# Power-MCU-Breakout.net
KiCad netlist of a schematic drawn in Altium Designer
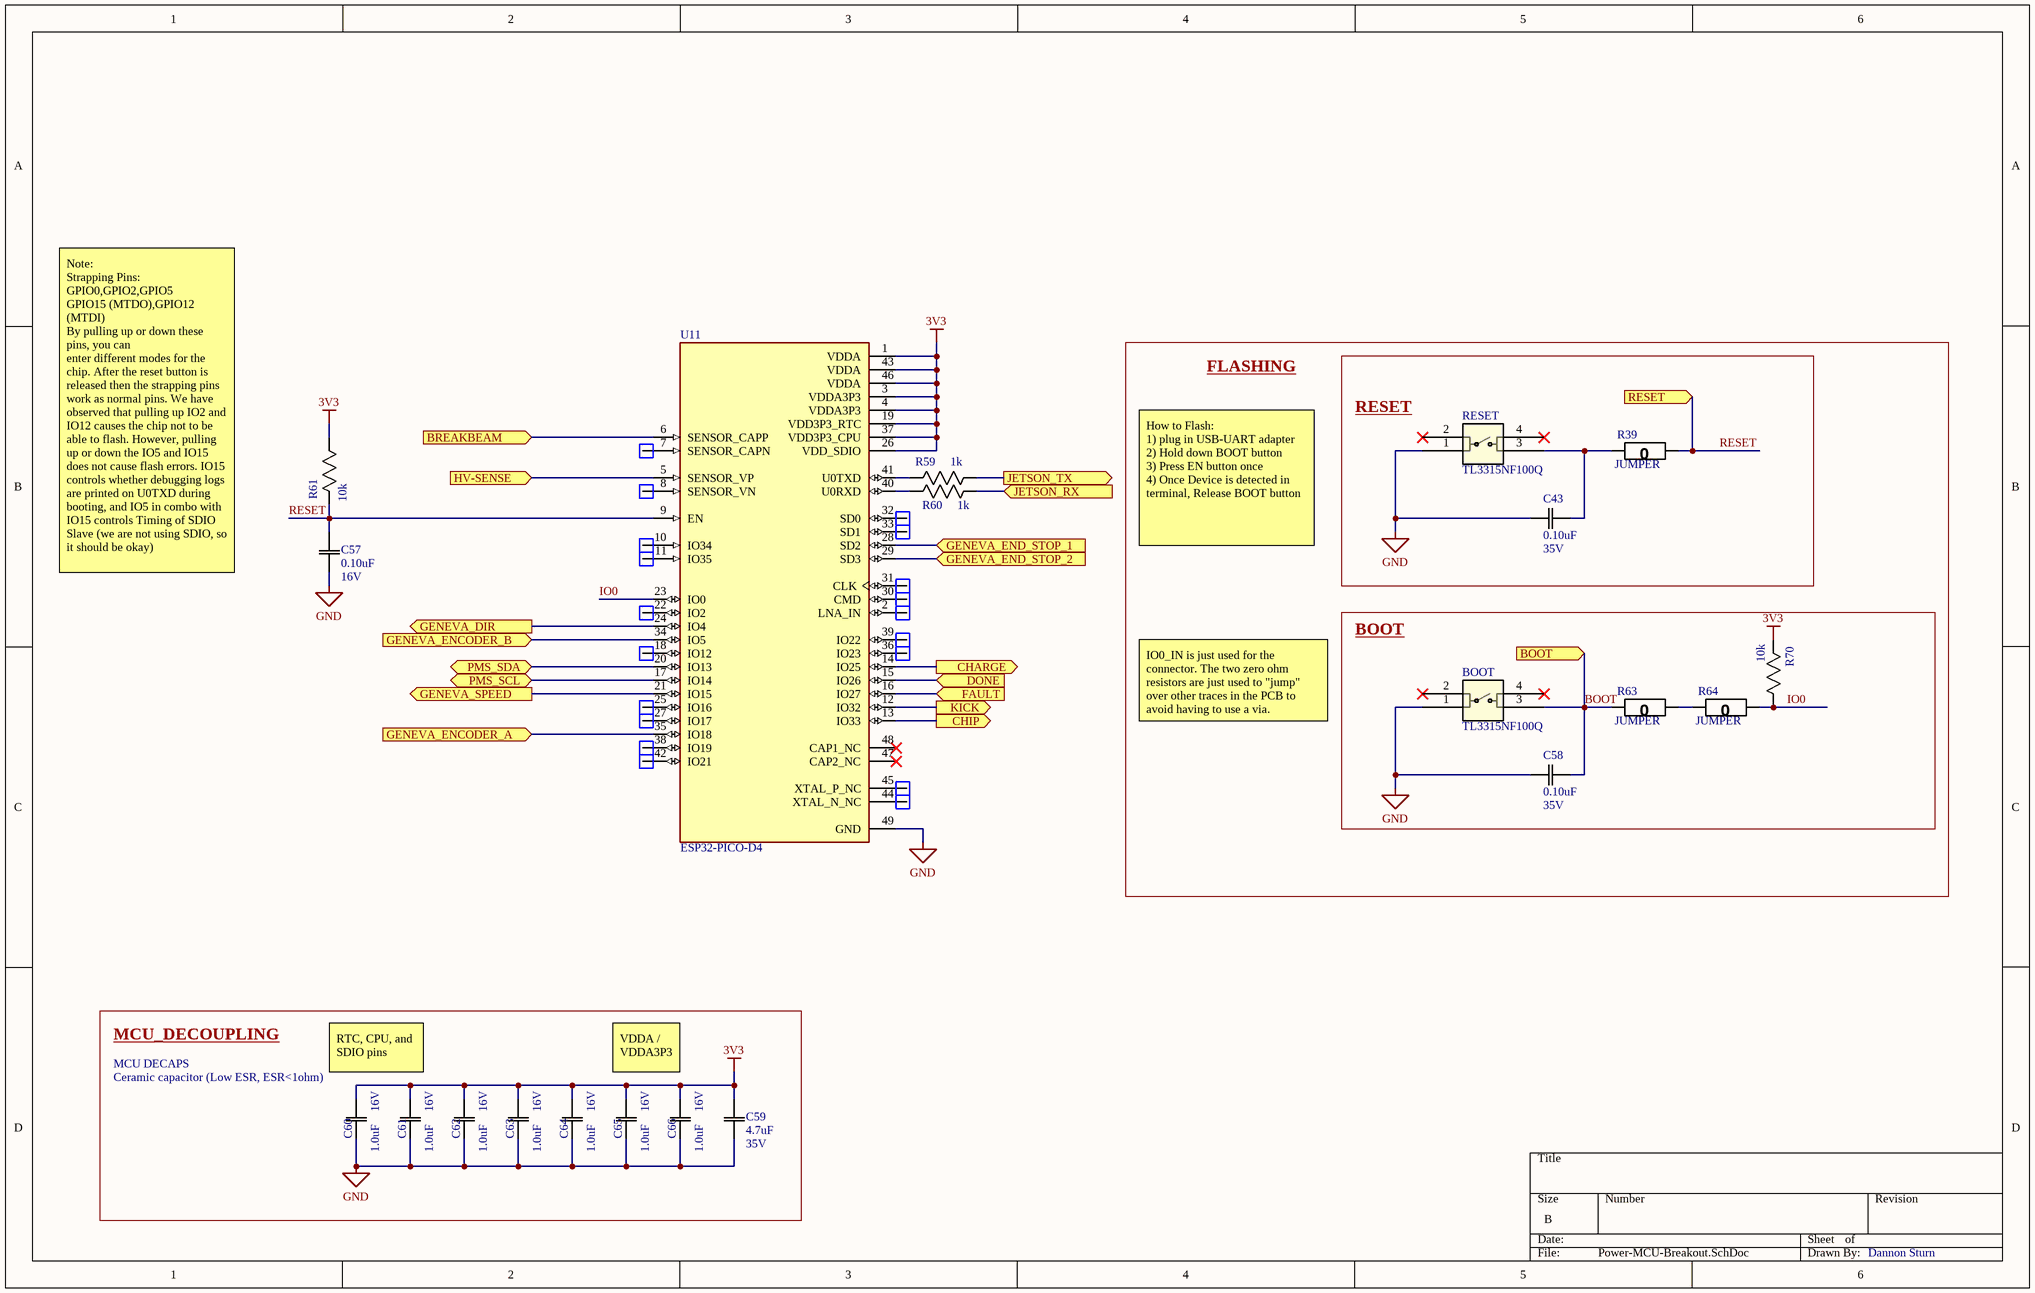
[diagram p0: Power-MCU-Breakout.SchDoc]

(export (version "E")
  (design (tool "Eeschema 10.0.6"))
  (components
    (comp (ref "1")
      (value "Breakout Pin 0603")
      (footprint "BreakoutPin 0603")
      (description "0603 breakout pad")
      (libsource (lib "IC_Library") (part "Breakout Pin 0603"))
    )
    (comp (ref "2")
      (value "Breakout Pin 0603")
      (footprint "BreakoutPin 0603")
      (description "0603 breakout pad")
      (libsource (lib "IC_Library") (part "Breakout Pin 0603"))
    )
    (comp (ref "3")
      (value "Breakout Pin 0603")
      (footprint "BreakoutPin 0603")
      (description "0603 breakout pad")
      (libsource (lib "IC_Library") (part "Breakout Pin 0603"))
    )
    (comp (ref "7")
      (value "Breakout Pin 0603")
      (footprint "BreakoutPin 0603")
      (description "0603 breakout pad")
      (libsource (lib "IC_Library") (part "Breakout Pin 0603"))
    )
    (comp (ref "8")
      (value "Breakout Pin 0603")
      (footprint "BreakoutPin 0603")
      (description "0603 breakout pad")
      (libsource (lib "IC_Library") (part "Breakout Pin 0603"))
    )
    (comp (ref "10")
      (value "Breakout Pin 0603")
      (footprint "BreakoutPin 0603")
      (description "0603 breakout pad")
      (libsource (lib "IC_Library") (part "Breakout Pin 0603"))
    )
    (comp (ref "11")
      (value "Breakout Pin 0603")
      (footprint "BreakoutPin 0603")
      (description "0603 breakout pad")
      (libsource (lib "IC_Library") (part "Breakout Pin 0603"))
    )
    (comp (ref "18")
      (value "Breakout Pin 0603")
      (footprint "BreakoutPin 0603")
      (description "0603 breakout pad")
      (libsource (lib "IC_Library") (part "Breakout Pin 0603"))
    )
    (comp (ref "22")
      (value "Breakout Pin 0603")
      (footprint "BreakoutPin 0603")
      (description "0603 breakout pad")
      (libsource (lib "IC_Library") (part "Breakout Pin 0603"))
    )
    (comp (ref "25")
      (value "Breakout Pin 0603")
      (footprint "BreakoutPin 0603")
      (description "0603 breakout pad")
      (libsource (lib "IC_Library") (part "Breakout Pin 0603"))
    )
    (comp (ref "27")
      (value "Breakout Pin 0603")
      (footprint "BreakoutPin 0603")
      (description "0603 breakout pad")
      (libsource (lib "IC_Library") (part "Breakout Pin 0603"))
    )
    (comp (ref "30")
      (value "Breakout Pin 0603")
      (footprint "BreakoutPin 0603")
      (description "0603 breakout pad")
      (libsource (lib "IC_Library") (part "Breakout Pin 0603"))
    )
    (comp (ref "31")
      (value "Breakout Pin 0603")
      (footprint "BreakoutPin 0603")
      (description "0603 breakout pad")
      (libsource (lib "IC_Library") (part "Breakout Pin 0603"))
    )
    (comp (ref "32")
      (value "Breakout Pin 0603")
      (footprint "BreakoutPin 0603")
      (description "0603 breakout pad")
      (libsource (lib "IC_Library") (part "Breakout Pin 0603"))
    )
    (comp (ref "33")
      (value "Breakout Pin 0603")
      (footprint "BreakoutPin 0603")
      (description "0603 breakout pad")
      (libsource (lib "IC_Library") (part "Breakout Pin 0603"))
    )
    (comp (ref "36")
      (value "Breakout Pin 0603")
      (footprint "BreakoutPin 0603")
      (description "0603 breakout pad")
      (libsource (lib "IC_Library") (part "Breakout Pin 0603"))
    )
    (comp (ref "42")
      (value "Breakout Pin 0603")
      (footprint "BreakoutPin 0603")
      (description "0603 breakout pad")
      (libsource (lib "IC_Library") (part "Breakout Pin 0603"))
    )
    (comp (ref "44")
      (value "Breakout Pin 0603")
      (footprint "BreakoutPin 0603")
      (description "0603 breakout pad")
      (libsource (lib "IC_Library") (part "Breakout Pin 0603"))
    )
    (comp (ref "45")
      (value "Breakout Pin 0603")
      (footprint "BreakoutPin 0603")
      (description "0603 breakout pad")
      (libsource (lib "IC_Library") (part "Breakout Pin 0603"))
    )
    (comp (ref "BOOT")
      (value "TL3315NF100Q")
      (footprint "SW_TL3315NF100Q")
      (description "Tactile Switch SPST-NO Top Actuated Surface Mount, 0.55mm Height")
      (fields
        (field (name "PART NUMBER") "SW PUSH TL3315")
        (field (name "COPYRIGHT") "Copyright (C) 2022 Ultra Librarian. All rights reserved.")
      )
      (libsource (lib "Switch_Library") (part "SW PUSH TL3315"))
    )
    (comp (ref "C43")
      (value "0.10uF")
      (footprint "0603")
      (description "CAP CER 0.10UF 35V X7R 0603")
      (fields
        (field (name "TOLERANCE") "10%")
        (field (name "RATING") "35V")
        (field (name "PART NUMBER") "CAP 0.10uF 35V 0603")
      )
      (libsource (lib "capacitor_library") (part "CAP 0.10uF 35V 0603"))
    )
    (comp (ref "C57")
      (value "0.10uF")
      (footprint "0603")
      (description "CAP CER 0.10UF 16V X5R 0603")
      (fields
        (field (name "TOLERANCE") "10%")
        (field (name "RATING") "16V")
        (field (name "PART NUMBER") "CAP 0.10uF 16V")
      )
      (libsource (lib "capacitor_library") (part "CAP 0.10uF 16V"))
    )
    (comp (ref "C58")
      (value "0.10uF")
      (footprint "0603")
      (description "CAP CER 0.10UF 35V X7R 0603")
      (fields
        (field (name "TOLERANCE") "10%")
        (field (name "RATING") "35V")
        (field (name "PART NUMBER") "CAP 0.10uF 35V")
      )
      (libsource (lib "capacitor_library") (part "CAP 0.10uF 35V"))
    )
    (comp (ref "C59")
      (value "4.7uF")
      (footprint "0603")
      (description "CAP CER 4.7UF 35V X7R 0603/0805")
      (fields
        (field (name "TOLERANCE") "10%")
        (field (name "RATING") "35V")
        (field (name "PART NUMBER") "CAP 4.7uF 35V")
      )
      (libsource (lib "capacitor_library") (part "CAP 4.7uF 35V"))
    )
    (comp (ref "C60")
      (value "1.0uF")
      (footprint "0603")
      (description "CAP CER 1.0UF 16V X5R 0603/0805")
      (fields
        (field (name "TOLERANCE") "10%")
        (field (name "RATING") "16V")
        (field (name "PART NUMBER") "CAP 1.0uF 16V")
      )
      (libsource (lib "capacitor_library") (part "CAP 1.0uF 16V"))
    )
    (comp (ref "C61")
      (value "1.0uF")
      (footprint "0603")
      (description "CAP CER 1.0UF 16V X5R 0603/0805")
      (fields
        (field (name "TOLERANCE") "10%")
        (field (name "RATING") "16V")
        (field (name "PART NUMBER") "CAP 1.0uF 16V")
      )
      (libsource (lib "capacitor_library") (part "CAP 1.0uF 16V"))
    )
    (comp (ref "C62")
      (value "1.0uF")
      (footprint "0603")
      (description "CAP CER 1.0UF 16V X5R 0603/0805")
      (fields
        (field (name "TOLERANCE") "10%")
        (field (name "RATING") "16V")
        (field (name "PART NUMBER") "CAP 1.0uF 16V")
      )
      (libsource (lib "capacitor_library") (part "CAP 1.0uF 16V"))
    )
    (comp (ref "C63")
      (value "1.0uF")
      (footprint "0603")
      (description "CAP CER 1.0UF 16V X5R 0603/0805")
      (fields
        (field (name "TOLERANCE") "10%")
        (field (name "RATING") "16V")
        (field (name "PART NUMBER") "CAP 1.0uF 16V")
      )
      (libsource (lib "capacitor_library") (part "CAP 1.0uF 16V"))
    )
    (comp (ref "C64")
      (value "1.0uF")
      (footprint "0603")
      (description "CAP CER 1.0UF 16V X5R 0603/0805")
      (fields
        (field (name "TOLERANCE") "10%")
        (field (name "RATING") "16V")
        (field (name "PART NUMBER") "CAP 1.0uF 16V")
      )
      (libsource (lib "capacitor_library") (part "CAP 1.0uF 16V"))
    )
    (comp (ref "C65")
      (value "1.0uF")
      (footprint "0603")
      (description "CAP CER 1.0UF 16V X5R 0603/0805")
      (fields
        (field (name "TOLERANCE") "10%")
        (field (name "RATING") "16V")
        (field (name "PART NUMBER") "CAP 1.0uF 16V")
      )
      (libsource (lib "capacitor_library") (part "CAP 1.0uF 16V"))
    )
    (comp (ref "C66")
      (value "1.0uF")
      (footprint "0603")
      (description "CAP CER 1.0UF 16V X5R 0603/0805")
      (fields
        (field (name "TOLERANCE") "10%")
        (field (name "RATING") "16V")
        (field (name "PART NUMBER") "CAP 1.0uF 16V")
      )
      (libsource (lib "capacitor_library") (part "CAP 1.0uF 16V"))
    )
    (comp (ref "R39")
      (value "JUMPER")
      (footprint "0603")
      (description "RES SMD 0 OHM JUMPER GENERIC 0603")
      (fields (field (name "PART NUMBER") "RES 0 JUMPER"))
      (libsource (lib "Resistor_Library") (part "RES 0 JUMPER"))
    )
    (comp (ref "R59")
      (value "1k")
      (footprint "0603")
      (description "RES SMD 1K OHM 1% 1/8W 0603")
      (fields (field (name "TOLERANCE") "1%") (field (name "PART NUMBER") "RES 1k 1/8W"))
      (libsource (lib "Resistor_Library") (part "RES 1k 1/8W"))
    )
    (comp (ref "R60")
      (value "1k")
      (footprint "0603")
      (description "RES SMD 1K OHM 1% 1/8W 0603")
      (fields (field (name "TOLERANCE") "1%") (field (name "PART NUMBER") "RES 1k 1/8W"))
      (libsource (lib "Resistor_Library") (part "RES 1k 1/8W"))
    )
    (comp (ref "R61")
      (value "10k")
      (footprint "0603")
      (description "RES SMD 10K OHM 5% 1/8W 0603")
      (fields (field (name "TOLERANCE") "5%") (field (name "PART NUMBER") "RES 10k 1/8W - 5%"))
      (libsource (lib "Resistor_Library") (part "RES 10k 1/8W 5%"))
    )
    (comp (ref "R63")
      (value "JUMPER")
      (footprint "0603")
      (description "RES SMD 0 OHM JUMPER GENERIC 0603")
      (fields (field (name "PART NUMBER") "RES 0 JUMPER"))
      (libsource (lib "Resistor_Library") (part "RES 0 JUMPER"))
    )
    (comp (ref "R64")
      (value "JUMPER")
      (footprint "0603")
      (description "RES SMD 0 OHM JUMPER GENERIC 0603")
      (fields (field (name "PART NUMBER") "RES 0 JUMPER"))
      (libsource (lib "Resistor_Library") (part "RES 0 JUMPER"))
    )
    (comp (ref "R70")
      (value "10k")
      (footprint "0603")
      (description "RES SMD 10K OHM 5% 1/8W 0603")
      (fields (field (name "TOLERANCE") "5%") (field (name "PART NUMBER") "RES 10k 1/8W - 5%"))
      (libsource (lib "") (part "RES 10k 1/8W 5%_1"))
    )
    (comp (ref "RESET")
      (value "TL3315NF100Q")
      (footprint "SW_TL3315NF100Q")
      (description "Tactile Switch SPST-NO Top Actuated Surface Mount, 0.55mm Height")
      (fields
        (field (name "PART NUMBER") "SW PUSH TL3315")
        (field (name "COPYRIGHT") "Copyright (C) 2022 Ultra Librarian. All rights reserved.")
      )
      (libsource (lib "Switch_Library") (part "SW PUSH TL3315"))
    )
    (comp (ref "U11")
      (value "ESP32-PICO-D4")
      (footprint "PQFN50P700X700X104-49N - BigPads")
      (description "RX TXRX MOD WIFI SURFACE MOUNT")
      (fields (field (name "MF") "Espressif Systems"))
      (libsource (lib "IC_Library") (part "ESP32-PICO-D4"))
    )
  )
  (nets
    (net (code "1") (name "/BOOT") (class "Default")
      (node (ref "BOOT") (pin "3") (pinfunction "3_3") (pintype "passive"))
      (node (ref "C58") (pin "2") (pinfunction "C2_2") (pintype "passive"))
      (node (ref "R63") (pin "2") (pinfunction "R2_2") (pintype "passive"))
    )
    (net (code "2") (name "/BREAKBEAM") (class "Default")
      (node (ref "U11") (pin "6") (pinfunction "SENSOR_CAPP_6") (pintype "input"))
    )
    (net (code "3") (name "/CHARGE") (class "Default")
      (node (ref "U11") (pin "14") (pinfunction "IO25_14") (pintype "bidirectional"))
    )
    (net (code "4") (name "/CHIP") (class "Default")
      (node (ref "U11") (pin "13") (pinfunction "IO33_13") (pintype "bidirectional"))
    )
    (net (code "5") (name "/DONE") (class "Default")
      (node (ref "U11") (pin "15") (pinfunction "IO26_15") (pintype "bidirectional"))
    )
    (net (code "6") (name "/FAULT") (class "Default")
      (node (ref "U11") (pin "16") (pinfunction "IO27_16") (pintype "bidirectional"))
    )
    (net (code "7") (name "/GENEVA_DIR") (class "Default")
      (node (ref "U11") (pin "24") (pinfunction "IO4_24") (pintype "bidirectional"))
    )
    (net (code "8") (name "/GENEVA_ENCODER_A") (class "Default")
      (node (ref "U11") (pin "35") (pinfunction "IO18_35") (pintype "bidirectional"))
    )
    (net (code "9") (name "/GENEVA_ENCODER_B") (class "Default")
      (node (ref "U11") (pin "34") (pinfunction "IO5_34") (pintype "bidirectional"))
    )
    (net (code "10") (name "/GENEVA_END_STOP_1") (class "Default")
      (node (ref "U11") (pin "28") (pinfunction "SD2_28") (pintype "bidirectional"))
    )
    (net (code "11") (name "/GENEVA_END_STOP_2") (class "Default")
      (node (ref "U11") (pin "29") (pinfunction "SD3_29") (pintype "bidirectional"))
    )
    (net (code "12") (name "/GENEVA_SPEED") (class "Default")
      (node (ref "U11") (pin "21") (pinfunction "IO15_21") (pintype "bidirectional"))
    )
    (net (code "13") (name "/HV-SENSE") (class "Default")
      (node (ref "U11") (pin "5") (pinfunction "SENSOR_VP_5") (pintype "input"))
    )
    (net (code "14") (name "/IO0") (class "Default")
      (node (ref "R64") (pin "1") (pinfunction "R1_1") (pintype "passive"))
      (node (ref "R70") (pin "1") (pinfunction "R1_1") (pintype "passive"))
      (node (ref "U11") (pin "23") (pinfunction "IO0_23") (pintype "bidirectional"))
    )
    (net (code "15") (name "/JETSON_RX") (class "Default")
      (node (ref "R60") (pin "1") (pinfunction "R1_1") (pintype "passive"))
    )
    (net (code "16") (name "/JETSON_TX") (class "Default")
      (node (ref "R59") (pin "1") (pinfunction "R1_1") (pintype "passive"))
    )
    (net (code "17") (name "/KICK") (class "Default")
      (node (ref "U11") (pin "12") (pinfunction "IO32_12") (pintype "bidirectional"))
    )
    (net (code "18") (name "/PMS_SCL") (class "Default")
      (node (ref "U11") (pin "17") (pinfunction "IO14_17") (pintype "bidirectional"))
    )
    (net (code "19") (name "/PMS_SDA") (class "Default")
      (node (ref "U11") (pin "20") (pinfunction "IO13_20") (pintype "bidirectional"))
    )
    (net (code "20") (name "/RESET") (class "Default")
      (node (ref "C57") (pin "2") (pinfunction "C2_2") (pintype "passive"))
      (node (ref "R39") (pin "1") (pinfunction "R1_1") (pintype "passive"))
      (node (ref "R61") (pin "2") (pinfunction "R2_2") (pintype "passive"))
      (node (ref "U11") (pin "9") (pinfunction "EN_9") (pintype "input"))
    )
    (net (code "21") (name "3V3") (class "Default")
      (node (ref "C59") (pin "2") (pinfunction "C2_2") (pintype "passive"))
      (node (ref "C60") (pin "2") (pinfunction "C2_2") (pintype "passive"))
      (node (ref "C61") (pin "2") (pinfunction "C2_2") (pintype "passive"))
      (node (ref "C62") (pin "2") (pinfunction "C2_2") (pintype "passive"))
      (node (ref "C63") (pin "2") (pinfunction "C2_2") (pintype "passive"))
      (node (ref "C64") (pin "2") (pinfunction "C2_2") (pintype "passive"))
      (node (ref "C65") (pin "2") (pinfunction "C2_2") (pintype "passive"))
      (node (ref "C66") (pin "2") (pinfunction "C2_2") (pintype "passive"))
      (node (ref "R61") (pin "1") (pinfunction "R1_1") (pintype "passive"))
      (node (ref "R70") (pin "2") (pinfunction "R2_2") (pintype "passive"))
      (node (ref "U11") (pin "1") (pinfunction "VDDA_1") (pintype "power_in"))
      (node (ref "U11") (pin "19") (pinfunction "VDD3P3_RTC_19") (pintype "power_in"))
      (node (ref "U11") (pin "26") (pinfunction "VDD_SDIO_26") (pintype "power_in"))
      (node (ref "U11") (pin "3") (pinfunction "VDDA3P3_3") (pintype "power_in"))
      (node (ref "U11") (pin "37") (pinfunction "VDD3P3_CPU_37") (pintype "power_in"))
      (node (ref "U11") (pin "4") (pinfunction "VDDA3P3_4") (pintype "power_in"))
      (node (ref "U11") (pin "43") (pinfunction "VDDA_43") (pintype "power_in"))
      (node (ref "U11") (pin "46") (pinfunction "VDDA_46") (pintype "power_in"))
    )
    (net (code "22") (name "GND") (class "Default")
      (node (ref "BOOT") (pin "1") (pinfunction "1_1") (pintype "passive"))
      (node (ref "C43") (pin "1") (pinfunction "C1_1") (pintype "passive"))
      (node (ref "C57") (pin "1") (pinfunction "C1_1") (pintype "passive"))
      (node (ref "C58") (pin "1") (pinfunction "C1_1") (pintype "passive"))
      (node (ref "C59") (pin "1") (pinfunction "C1_1") (pintype "passive"))
      (node (ref "C60") (pin "1") (pinfunction "C1_1") (pintype "passive"))
      (node (ref "C61") (pin "1") (pinfunction "C1_1") (pintype "passive"))
      (node (ref "C62") (pin "1") (pinfunction "C1_1") (pintype "passive"))
      (node (ref "C63") (pin "1") (pinfunction "C1_1") (pintype "passive"))
      (node (ref "C64") (pin "1") (pinfunction "C1_1") (pintype "passive"))
      (node (ref "C65") (pin "1") (pinfunction "C1_1") (pintype "passive"))
      (node (ref "C66") (pin "1") (pinfunction "C1_1") (pintype "passive"))
      (node (ref "RESET") (pin "1") (pinfunction "1_1") (pintype "passive"))
      (node (ref "U11") (pin "49") (pinfunction "GND_49") (pintype "power_in"))
    )
    (net (code "23") (name "Net-(1-BRKOUT)") (class "Default")
      (node (ref "1") (pin "1") (pinfunction "BRKOUT_1") (pintype "passive"))
      (node (ref "U11") (pin "39") (pinfunction "IO22_39") (pintype "bidirectional"))
    )
    (net (code "24") (name "Net-(2-BRKOUT)") (class "Default")
      (node (ref "2") (pin "1") (pinfunction "BRKOUT_1") (pintype "passive"))
      (node (ref "U11") (pin "2") (pinfunction "LNA_IN_2") (pintype "bidirectional"))
    )
    (net (code "25") (name "Net-(3-BRKOUT)") (class "Default")
      (node (ref "3") (pin "1") (pinfunction "BRKOUT_1") (pintype "passive"))
      (node (ref "U11") (pin "38") (pinfunction "IO19_38") (pintype "bidirectional"))
    )
    (net (code "26") (name "Net-(7-BRKOUT)") (class "Default")
      (node (ref "7") (pin "1") (pinfunction "BRKOUT_1") (pintype "passive"))
      (node (ref "U11") (pin "7") (pinfunction "SENSOR_CAPN_7") (pintype "input"))
    )
    (net (code "27") (name "Net-(8-BRKOUT)") (class "Default")
      (node (ref "8") (pin "1") (pinfunction "BRKOUT_1") (pintype "passive"))
      (node (ref "U11") (pin "8") (pinfunction "SENSOR_VN_8") (pintype "input"))
    )
    (net (code "28") (name "Net-(10-BRKOUT)") (class "Default")
      (node (ref "10") (pin "1") (pinfunction "BRKOUT_1") (pintype "passive"))
      (node (ref "U11") (pin "10") (pinfunction "IO34_10") (pintype "input"))
    )
    (net (code "29") (name "Net-(11-BRKOUT)") (class "Default")
      (node (ref "11") (pin "1") (pinfunction "BRKOUT_1") (pintype "passive"))
      (node (ref "U11") (pin "11") (pinfunction "IO35_11") (pintype "input"))
    )
    (net (code "30") (name "Net-(18-BRKOUT)") (class "Default")
      (node (ref "18") (pin "1") (pinfunction "BRKOUT_1") (pintype "passive"))
      (node (ref "U11") (pin "18") (pinfunction "IO12_18") (pintype "bidirectional"))
    )
    (net (code "31") (name "Net-(22-BRKOUT)") (class "Default")
      (node (ref "22") (pin "1") (pinfunction "BRKOUT_1") (pintype "passive"))
      (node (ref "U11") (pin "22") (pinfunction "IO2_22") (pintype "bidirectional"))
    )
    (net (code "32") (name "Net-(25-BRKOUT)") (class "Default")
      (node (ref "25") (pin "1") (pinfunction "BRKOUT_1") (pintype "passive"))
      (node (ref "U11") (pin "25") (pinfunction "IO16_25") (pintype "bidirectional"))
    )
    (net (code "33") (name "Net-(27-BRKOUT)") (class "Default")
      (node (ref "27") (pin "1") (pinfunction "BRKOUT_1") (pintype "passive"))
      (node (ref "U11") (pin "27") (pinfunction "IO17_27") (pintype "bidirectional"))
    )
    (net (code "34") (name "Net-(30-BRKOUT)") (class "Default")
      (node (ref "30") (pin "1") (pinfunction "BRKOUT_1") (pintype "passive"))
      (node (ref "U11") (pin "30") (pinfunction "CMD_30") (pintype "bidirectional"))
    )
    (net (code "35") (name "Net-(31-BRKOUT)") (class "Default")
      (node (ref "31") (pin "1") (pinfunction "BRKOUT_1") (pintype "passive"))
      (node (ref "U11") (pin "31") (pinfunction "CLK_31") (pintype "bidirectional"))
    )
    (net (code "36") (name "Net-(32-BRKOUT)") (class "Default")
      (node (ref "32") (pin "1") (pinfunction "BRKOUT_1") (pintype "passive"))
      (node (ref "U11") (pin "32") (pinfunction "SD0_32") (pintype "bidirectional"))
    )
    (net (code "37") (name "Net-(33-BRKOUT)") (class "Default")
      (node (ref "33") (pin "1") (pinfunction "BRKOUT_1") (pintype "passive"))
      (node (ref "U11") (pin "33") (pinfunction "SD1_33") (pintype "bidirectional"))
    )
    (net (code "38") (name "Net-(36-BRKOUT)") (class "Default")
      (node (ref "36") (pin "1") (pinfunction "BRKOUT_1") (pintype "passive"))
      (node (ref "U11") (pin "36") (pinfunction "IO23_36") (pintype "bidirectional"))
    )
    (net (code "39") (name "Net-(42-BRKOUT)") (class "Default")
      (node (ref "42") (pin "1") (pinfunction "BRKOUT_1") (pintype "passive"))
      (node (ref "U11") (pin "42") (pinfunction "IO21_42") (pintype "bidirectional"))
    )
    (net (code "40") (name "Net-(44-BRKOUT)") (class "Default")
      (node (ref "44") (pin "1") (pinfunction "BRKOUT_1") (pintype "passive"))
      (node (ref "U11") (pin "44") (pinfunction "XTAL_N_NC_44") (pintype "passive"))
    )
    (net (code "41") (name "Net-(45-BRKOUT)") (class "Default")
      (node (ref "45") (pin "1") (pinfunction "BRKOUT_1") (pintype "passive"))
      (node (ref "U11") (pin "45") (pinfunction "XTAL_P_NC_45") (pintype "passive"))
    )
    (net (code "42") (name "Net-(C43-C2)") (class "Default")
      (node (ref "C43") (pin "2") (pinfunction "C2_2") (pintype "passive"))
      (node (ref "R39") (pin "2") (pinfunction "R2_2") (pintype "passive"))
      (node (ref "RESET") (pin "3") (pinfunction "3_3") (pintype "passive"))
    )
    (net (code "43") (name "Net-(R59-R2)") (class "Default")
      (node (ref "R59") (pin "2") (pinfunction "R2_2") (pintype "passive"))
      (node (ref "U11") (pin "41") (pinfunction "U0TXD_41") (pintype "bidirectional"))
    )
    (net (code "44") (name "Net-(R60-R2)") (class "Default")
      (node (ref "R60") (pin "2") (pinfunction "R2_2") (pintype "passive"))
      (node (ref "U11") (pin "40") (pinfunction "U0RXD_40") (pintype "bidirectional"))
    )
    (net (code "45") (name "Net-(R63-R1)") (class "Default")
      (node (ref "R63") (pin "1") (pinfunction "R1_1") (pintype "passive"))
      (node (ref "R64") (pin "2") (pinfunction "R2_2") (pintype "passive"))
    )
    (net (code "46") (name "unconnected-(BOOT-Pad2)") (class "Default")
      (node (ref "BOOT") (pin "2") (pinfunction "2_2") (pintype "passive+no_connect"))
    )
    (net (code "47") (name "unconnected-(BOOT-Pad4)") (class "Default")
      (node (ref "BOOT") (pin "4") (pinfunction "4_4") (pintype "passive+no_connect"))
    )
    (net (code "48") (name "unconnected-(RESET-Pad2)") (class "Default")
      (node (ref "RESET") (pin "2") (pinfunction "2_2") (pintype "passive+no_connect"))
    )
    (net (code "49") (name "unconnected-(RESET-Pad4)") (class "Default")
      (node (ref "RESET") (pin "4") (pinfunction "4_4") (pintype "passive+no_connect"))
    )
    (net (code "50") (name "unconnected-(U11-CAP1_NC-Pad48)") (class "Default")
      (node (ref "U11") (pin "48") (pinfunction "CAP1_NC_48") (pintype "passive+no_connect"))
    )
    (net (code "51") (name "unconnected-(U11-CAP2_NC-Pad47)") (class "Default")
      (node (ref "U11") (pin "47") (pinfunction "CAP2_NC_47") (pintype "passive+no_connect"))
    )
  )
)
